# MCU.net
KiCad netlist of a schematic drawn in Altium Designer
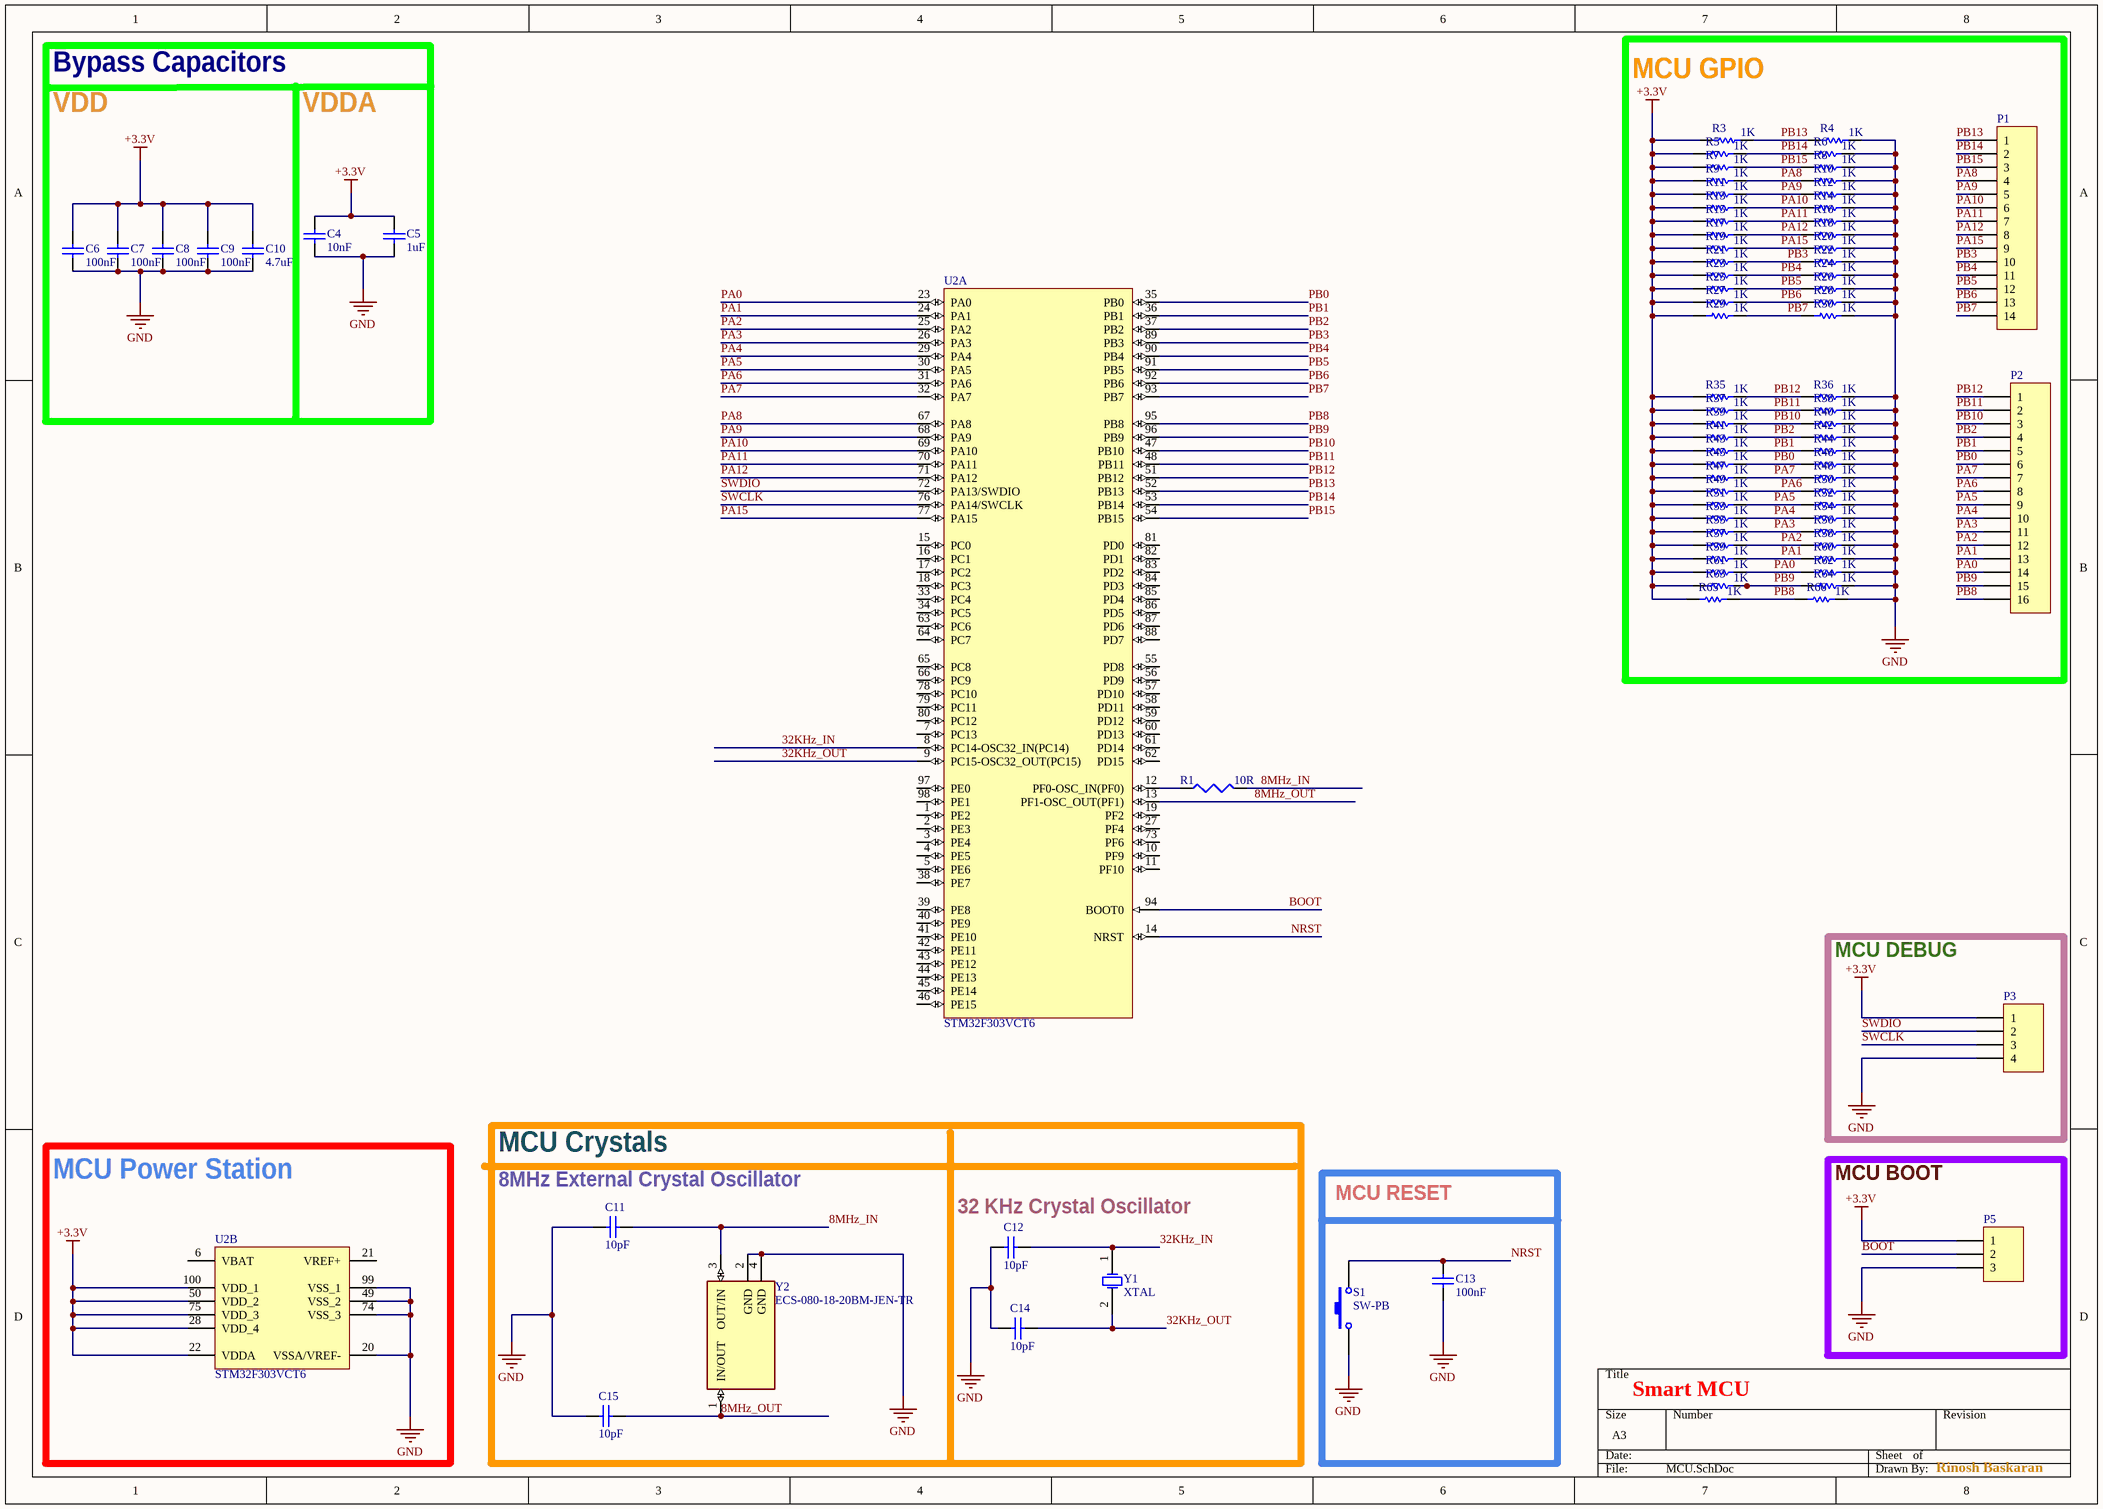
[diagram p0: MCU.SchDoc]

(export (version "E")
  (design (tool "Eeschema 10.0.6"))
  (components
    (comp (ref "C4")
      (value "10nF")
      (footprint "1608[0603]")
      (description "Capacitor (Semiconductor SIM Model)")
      (fields (field (name "Comment") "Cap Semi") (field (name "PUBLISHER") "Altium Limited"))
      (libsource (lib "Miscellaneous Devices") (part "Cap Semi"))
    )
    (comp (ref "C5")
      (value "1uF")
      (footprint "1608[0603]")
      (description "Capacitor (Semiconductor SIM Model)")
      (fields (field (name "Comment") "Cap Semi") (field (name "PUBLISHER") "Altium Limited"))
      (libsource (lib "Miscellaneous Devices") (part "Cap Semi"))
    )
    (comp (ref "C6")
      (value "100nF")
      (footprint "1608[0603]")
      (description "Capacitor (Semiconductor SIM Model)")
      (fields (field (name "Comment") "Cap Semi") (field (name "PUBLISHER") "Altium Limited"))
      (libsource (lib "Miscellaneous Devices") (part "Cap Semi"))
    )
    (comp (ref "C7")
      (value "100nF")
      (footprint "1608[0603]")
      (description "Capacitor (Semiconductor SIM Model)")
      (fields (field (name "Comment") "Cap Semi") (field (name "PUBLISHER") "Altium Limited"))
      (libsource (lib "Miscellaneous Devices") (part "Cap Semi"))
    )
    (comp (ref "C8")
      (value "100nF")
      (footprint "1608[0603]")
      (description "Capacitor (Semiconductor SIM Model)")
      (fields (field (name "Comment") "Cap Semi") (field (name "PUBLISHER") "Altium Limited"))
      (libsource (lib "Miscellaneous Devices") (part "Cap Semi"))
    )
    (comp (ref "C9")
      (value "100nF")
      (footprint "1608[0603]")
      (description "Capacitor (Semiconductor SIM Model)")
      (fields (field (name "Comment") "Cap Semi") (field (name "PUBLISHER") "Altium Limited"))
      (libsource (lib "Miscellaneous Devices") (part "Cap Semi"))
    )
    (comp (ref "C10")
      (value "4.7uF")
      (footprint "1608[0603]")
      (description "Capacitor (Semiconductor SIM Model)")
      (fields (field (name "Comment") "Cap Semi") (field (name "PUBLISHER") "Altium Limited"))
      (libsource (lib "Miscellaneous Devices") (part "Cap Semi"))
    )
    (comp (ref "C11")
      (value "10pF")
      (footprint "1608[0603]")
      (description "Capacitor (Semiconductor SIM Model)")
      (fields (field (name "Comment") "Cap Semi") (field (name "PUBLISHER") "Altium Limited"))
      (libsource (lib "Miscellaneous Devices") (part "Cap Semi"))
    )
    (comp (ref "C12")
      (value "10pF")
      (footprint "1608[0603]")
      (description "Capacitor (Semiconductor SIM Model)")
      (fields (field (name "Comment") "Cap Semi") (field (name "PUBLISHER") "Altium Limited"))
      (libsource (lib "Miscellaneous Devices") (part "Cap Semi"))
    )
    (comp (ref "C13")
      (value "100nF")
      (footprint "1608[0603]")
      (description "Capacitor (Semiconductor SIM Model)")
      (fields (field (name "Comment") "Cap Semi") (field (name "PUBLISHER") "Altium Limited"))
      (libsource (lib "Miscellaneous Devices") (part "Cap Semi"))
    )
    (comp (ref "C14")
      (value "10pF")
      (footprint "1608[0603]")
      (description "Capacitor (Semiconductor SIM Model)")
      (fields (field (name "Comment") "Cap Semi") (field (name "PUBLISHER") "Altium Limited"))
      (libsource (lib "Miscellaneous Devices") (part "Cap Semi"))
    )
    (comp (ref "C15")
      (value "10pF")
      (footprint "1608[0603]")
      (description "Capacitor (Semiconductor SIM Model)")
      (fields (field (name "Comment") "Cap Semi") (field (name "PUBLISHER") "Altium Limited"))
      (libsource (lib "Miscellaneous Devices") (part "Cap Semi"))
    )
    (comp (ref "P1")
      (value "Header 14")
      (footprint "MY_FE14")
      (description "Header, 14-Pin")
      (fields (field (name "ASID PART NUMBER") "Header 14-AS"))
      (libsource (lib "Mylib+Rev+4") (part "Header 14"))
    )
    (comp (ref "P2")
      (value "Header 16")
      (footprint "MY_FE16")
      (description "Header, 16-Pin")
      (fields (field (name "ASID PART NUMBER") "Header 16-AS"))
      (libsource (lib "Mylib+Rev+4") (part "Header 16"))
    )
    (comp (ref "P3")
      (value "Header 4")
      (footprint "My_1X04")
      (description "Header, 4-Pin")
      (fields (field (name "ASID PART NUMBER") "Header 4-AS"))
      (libsource (lib "Mylib+Rev+4") (part "Header 4"))
    )
    (comp (ref "P5")
      (value "Header 3")
      (footprint "My_1X03")
      (description "Header, 3-Pin")
      (fields (field (name "ASID PART NUMBER") "Header 3-AS"))
      (libsource (lib "Mylib+Rev+4") (part "Header 3"))
    )
    (comp (ref "R1")
      (value "10R")
      (footprint "J1-0603")
      (description "Resistor")
      (fields (field (name "Comment") "Res3") (field (name "PUBLISHER") "Altium Limited"))
      (libsource (lib "Miscellaneous Devices") (part "Res3"))
    )
    (comp (ref "R3")
      (value "1K")
      (footprint "MY_0805")
      (description "Standard resistor")
      (fields (field (name "ASID PART NUMBER") "Res-AS"))
      (libsource (lib "Mylib+Rev+4") (part "Res"))
    )
    (comp (ref "R4")
      (value "1K")
      (footprint "MY_0805")
      (description "Standard resistor")
      (fields (field (name "ASID PART NUMBER") "Res-AS"))
      (libsource (lib "Mylib+Rev+4") (part "Res"))
    )
    (comp (ref "R5")
      (value "1K")
      (footprint "MY_0805")
      (description "Standard resistor")
      (fields (field (name "ASID PART NUMBER") "Res-AS"))
      (libsource (lib "Mylib+Rev+4") (part "Res"))
    )
    (comp (ref "R6")
      (value "1K")
      (footprint "MY_0805")
      (description "Standard resistor")
      (fields (field (name "ASID PART NUMBER") "Res-AS"))
      (libsource (lib "Mylib+Rev+4") (part "Res"))
    )
    (comp (ref "R7")
      (value "1K")
      (footprint "MY_0805")
      (description "Standard resistor")
      (fields (field (name "ASID PART NUMBER") "Res-AS"))
      (libsource (lib "Mylib+Rev+4") (part "Res"))
    )
    (comp (ref "R8")
      (value "1K")
      (footprint "MY_0805")
      (description "Standard resistor")
      (fields (field (name "ASID PART NUMBER") "Res-AS"))
      (libsource (lib "Mylib+Rev+4") (part "Res"))
    )
    (comp (ref "R9")
      (value "1K")
      (footprint "MY_0805")
      (description "Standard resistor")
      (fields (field (name "ASID PART NUMBER") "Res-AS"))
      (libsource (lib "Mylib+Rev+4") (part "Res"))
    )
    (comp (ref "R10")
      (value "1K")
      (footprint "MY_0805")
      (description "Standard resistor")
      (fields (field (name "ASID PART NUMBER") "Res-AS"))
      (libsource (lib "Mylib+Rev+4") (part "Res"))
    )
    (comp (ref "R11")
      (value "1K")
      (footprint "MY_0805")
      (description "Standard resistor")
      (fields (field (name "ASID PART NUMBER") "Res-AS"))
      (libsource (lib "Mylib+Rev+4") (part "Res"))
    )
    (comp (ref "R12")
      (value "1K")
      (footprint "MY_0805")
      (description "Standard resistor")
      (fields (field (name "ASID PART NUMBER") "Res-AS"))
      (libsource (lib "Mylib+Rev+4") (part "Res"))
    )
    (comp (ref "R13")
      (value "1K")
      (footprint "MY_0805")
      (description "Standard resistor")
      (fields (field (name "ASID PART NUMBER") "Res-AS"))
      (libsource (lib "Mylib+Rev+4") (part "Res"))
    )
    (comp (ref "R14")
      (value "1K")
      (footprint "MY_0805")
      (description "Standard resistor")
      (fields (field (name "ASID PART NUMBER") "Res-AS"))
      (libsource (lib "Mylib+Rev+4") (part "Res"))
    )
    (comp (ref "R15")
      (value "1K")
      (footprint "MY_0805")
      (description "Standard resistor")
      (fields (field (name "ASID PART NUMBER") "Res-AS"))
      (libsource (lib "Mylib+Rev+4") (part "Res"))
    )
    (comp (ref "R16")
      (value "1K")
      (footprint "MY_0805")
      (description "Standard resistor")
      (fields (field (name "ASID PART NUMBER") "Res-AS"))
      (libsource (lib "Mylib+Rev+4") (part "Res"))
    )
    (comp (ref "R17")
      (value "1K")
      (footprint "MY_0805")
      (description "Standard resistor")
      (fields (field (name "ASID PART NUMBER") "Res-AS"))
      (libsource (lib "Mylib+Rev+4") (part "Res"))
    )
    (comp (ref "R18")
      (value "1K")
      (footprint "MY_0805")
      (description "Standard resistor")
      (fields (field (name "ASID PART NUMBER") "Res-AS"))
      (libsource (lib "Mylib+Rev+4") (part "Res"))
    )
    (comp (ref "R19")
      (value "1K")
      (footprint "MY_0805")
      (description "Standard resistor")
      (fields (field (name "ASID PART NUMBER") "Res-AS"))
      (libsource (lib "Mylib+Rev+4") (part "Res"))
    )
    (comp (ref "R20")
      (value "1K")
      (footprint "MY_0805")
      (description "Standard resistor")
      (fields (field (name "ASID PART NUMBER") "Res-AS"))
      (libsource (lib "Mylib+Rev+4") (part "Res"))
    )
    (comp (ref "R21")
      (value "1K")
      (footprint "MY_0805")
      (description "Standard resistor")
      (fields (field (name "ASID PART NUMBER") "Res-AS"))
      (libsource (lib "Mylib+Rev+4") (part "Res"))
    )
    (comp (ref "R22")
      (value "1K")
      (footprint "MY_0805")
      (description "Standard resistor")
      (fields (field (name "ASID PART NUMBER") "Res-AS"))
      (libsource (lib "Mylib+Rev+4") (part "Res"))
    )
    (comp (ref "R23")
      (value "1K")
      (footprint "MY_0805")
      (description "Standard resistor")
      (fields (field (name "ASID PART NUMBER") "Res-AS"))
      (libsource (lib "Mylib+Rev+4") (part "Res"))
    )
    (comp (ref "R24")
      (value "1K")
      (footprint "MY_0805")
      (description "Standard resistor")
      (fields (field (name "ASID PART NUMBER") "Res-AS"))
      (libsource (lib "Mylib+Rev+4") (part "Res"))
    )
    (comp (ref "R25")
      (value "1K")
      (footprint "MY_0805")
      (description "Standard resistor")
      (fields (field (name "ASID PART NUMBER") "Res-AS"))
      (libsource (lib "Mylib+Rev+4") (part "Res"))
    )
    (comp (ref "R26")
      (value "1K")
      (footprint "MY_0805")
      (description "Standard resistor")
      (fields (field (name "ASID PART NUMBER") "Res-AS"))
      (libsource (lib "Mylib+Rev+4") (part "Res"))
    )
    (comp (ref "R27")
      (value "1K")
      (footprint "MY_0805")
      (description "Standard resistor")
      (fields (field (name "ASID PART NUMBER") "Res-AS"))
      (libsource (lib "Mylib+Rev+4") (part "Res"))
    )
    (comp (ref "R28")
      (value "1K")
      (footprint "MY_0805")
      (description "Standard resistor")
      (fields (field (name "ASID PART NUMBER") "Res-AS"))
      (libsource (lib "Mylib+Rev+4") (part "Res"))
    )
    (comp (ref "R29")
      (value "1K")
      (footprint "MY_0805")
      (description "Standard resistor")
      (fields (field (name "ASID PART NUMBER") "Res-AS"))
      (libsource (lib "Mylib+Rev+4") (part "Res"))
    )
    (comp (ref "R30")
      (value "1K")
      (footprint "MY_0805")
      (description "Standard resistor")
      (fields (field (name "ASID PART NUMBER") "Res-AS"))
      (libsource (lib "Mylib+Rev+4") (part "Res"))
    )
    (comp (ref "R35")
      (value "1K")
      (footprint "MY_0805")
      (description "Standard resistor")
      (fields (field (name "ASID PART NUMBER") "Res-AS"))
      (libsource (lib "Mylib+Rev+4") (part "Res"))
    )
    (comp (ref "R36")
      (value "1K")
      (footprint "MY_0805")
      (description "Standard resistor")
      (fields (field (name "ASID PART NUMBER") "Res-AS"))
      (libsource (lib "Mylib+Rev+4") (part "Res"))
    )
    (comp (ref "R37")
      (value "1K")
      (footprint "MY_0805")
      (description "Standard resistor")
      (fields (field (name "ASID PART NUMBER") "Res-AS"))
      (libsource (lib "Mylib+Rev+4") (part "Res"))
    )
    (comp (ref "R38")
      (value "1K")
      (footprint "MY_0805")
      (description "Standard resistor")
      (fields (field (name "ASID PART NUMBER") "Res-AS"))
      (libsource (lib "Mylib+Rev+4") (part "Res"))
    )
    (comp (ref "R39")
      (value "1K")
      (footprint "MY_0805")
      (description "Standard resistor")
      (fields (field (name "ASID PART NUMBER") "Res-AS"))
      (libsource (lib "Mylib+Rev+4") (part "Res"))
    )
    (comp (ref "R40")
      (value "1K")
      (footprint "MY_0805")
      (description "Standard resistor")
      (fields (field (name "ASID PART NUMBER") "Res-AS"))
      (libsource (lib "Mylib+Rev+4") (part "Res"))
    )
    (comp (ref "R41")
      (value "1K")
      (footprint "MY_0805")
      (description "Standard resistor")
      (fields (field (name "ASID PART NUMBER") "Res-AS"))
      (libsource (lib "Mylib+Rev+4") (part "Res"))
    )
    (comp (ref "R42")
      (value "1K")
      (footprint "MY_0805")
      (description "Standard resistor")
      (fields (field (name "ASID PART NUMBER") "Res-AS"))
      (libsource (lib "Mylib+Rev+4") (part "Res"))
    )
    (comp (ref "R43")
      (value "1K")
      (footprint "MY_0805")
      (description "Standard resistor")
      (fields (field (name "ASID PART NUMBER") "Res-AS"))
      (libsource (lib "Mylib+Rev+4") (part "Res"))
    )
    (comp (ref "R44")
      (value "1K")
      (footprint "MY_0805")
      (description "Standard resistor")
      (fields (field (name "ASID PART NUMBER") "Res-AS"))
      (libsource (lib "Mylib+Rev+4") (part "Res"))
    )
    (comp (ref "R45")
      (value "1K")
      (footprint "MY_0805")
      (description "Standard resistor")
      (fields (field (name "ASID PART NUMBER") "Res-AS"))
      (libsource (lib "Mylib+Rev+4") (part "Res"))
    )
    (comp (ref "R46")
      (value "1K")
      (footprint "MY_0805")
      (description "Standard resistor")
      (fields (field (name "ASID PART NUMBER") "Res-AS"))
      (libsource (lib "Mylib+Rev+4") (part "Res"))
    )
    (comp (ref "R47")
      (value "1K")
      (footprint "MY_0805")
      (description "Standard resistor")
      (fields (field (name "ASID PART NUMBER") "Res-AS"))
      (libsource (lib "Mylib+Rev+4") (part "Res"))
    )
    (comp (ref "R48")
      (value "1K")
      (footprint "MY_0805")
      (description "Standard resistor")
      (fields (field (name "ASID PART NUMBER") "Res-AS"))
      (libsource (lib "Mylib+Rev+4") (part "Res"))
    )
    (comp (ref "R49")
      (value "1K")
      (footprint "MY_0805")
      (description "Standard resistor")
      (fields (field (name "ASID PART NUMBER") "Res-AS"))
      (libsource (lib "Mylib+Rev+4") (part "Res"))
    )
    (comp (ref "R50")
      (value "1K")
      (footprint "MY_0805")
      (description "Standard resistor")
      (fields (field (name "ASID PART NUMBER") "Res-AS"))
      (libsource (lib "Mylib+Rev+4") (part "Res"))
    )
    (comp (ref "R51")
      (value "1K")
      (footprint "MY_0805")
      (description "Standard resistor")
      (fields (field (name "ASID PART NUMBER") "Res-AS"))
      (libsource (lib "Mylib+Rev+4") (part "Res"))
    )
    (comp (ref "R52")
      (value "1K")
      (footprint "MY_0805")
      (description "Standard resistor")
      (fields (field (name "ASID PART NUMBER") "Res-AS"))
      (libsource (lib "Mylib+Rev+4") (part "Res"))
    )
    (comp (ref "R53")
      (value "1K")
      (footprint "MY_0805")
      (description "Standard resistor")
      (fields (field (name "ASID PART NUMBER") "Res-AS"))
      (libsource (lib "Mylib+Rev+4") (part "Res"))
    )
    (comp (ref "R54")
      (value "1K")
      (footprint "MY_0805")
      (description "Standard resistor")
      (fields (field (name "ASID PART NUMBER") "Res-AS"))
      (libsource (lib "Mylib+Rev+4") (part "Res"))
    )
    (comp (ref "R55")
      (value "1K")
      (footprint "MY_0805")
      (description "Standard resistor")
      (fields (field (name "ASID PART NUMBER") "Res-AS"))
      (libsource (lib "Mylib+Rev+4") (part "Res"))
    )
    (comp (ref "R56")
      (value "1K")
      (footprint "MY_0805")
      (description "Standard resistor")
      (fields (field (name "ASID PART NUMBER") "Res-AS"))
      (libsource (lib "Mylib+Rev+4") (part "Res"))
    )
    (comp (ref "R57")
      (value "1K")
      (footprint "MY_0805")
      (description "Standard resistor")
      (fields (field (name "ASID PART NUMBER") "Res-AS"))
      (libsource (lib "Mylib+Rev+4") (part "Res"))
    )
    (comp (ref "R58")
      (value "1K")
      (footprint "MY_0805")
      (description "Standard resistor")
      (fields (field (name "ASID PART NUMBER") "Res-AS"))
      (libsource (lib "Mylib+Rev+4") (part "Res"))
    )
    (comp (ref "R59")
      (value "1K")
      (footprint "MY_0805")
      (description "Standard resistor")
      (fields (field (name "ASID PART NUMBER") "Res-AS"))
      (libsource (lib "Mylib+Rev+4") (part "Res"))
    )
    (comp (ref "R60")
      (value "1K")
      (footprint "MY_0805")
      (description "Standard resistor")
      (fields (field (name "ASID PART NUMBER") "Res-AS"))
      (libsource (lib "Mylib+Rev+4") (part "Res"))
    )
    (comp (ref "R61")
      (value "1K")
      (footprint "MY_0805")
      (description "Standard resistor")
      (fields (field (name "ASID PART NUMBER") "Res-AS"))
      (libsource (lib "Mylib+Rev+4") (part "Res"))
    )
    (comp (ref "R62")
      (value "1K")
      (footprint "MY_0805")
      (description "Standard resistor")
      (fields (field (name "ASID PART NUMBER") "Res-AS"))
      (libsource (lib "Mylib+Rev+4") (part "Res"))
    )
    (comp (ref "R63")
      (value "1K")
      (footprint "MY_0805")
      (description "Standard resistor")
      (fields (field (name "ASID PART NUMBER") "Res-AS"))
      (libsource (lib "Mylib+Rev+4") (part "Res"))
    )
    (comp (ref "R64")
      (value "1K")
      (footprint "MY_0805")
      (description "Standard resistor")
      (fields (field (name "ASID PART NUMBER") "Res-AS"))
      (libsource (lib "Mylib+Rev+4") (part "Res"))
    )
    (comp (ref "R65")
      (value "1K")
      (footprint "MY_0805")
      (description "Standard resistor")
      (fields (field (name "ASID PART NUMBER") "Res-AS"))
      (libsource (lib "Mylib+Rev+4") (part "Res"))
    )
    (comp (ref "R66")
      (value "1K")
      (footprint "MY_0805")
      (description "Standard resistor")
      (fields (field (name "ASID PART NUMBER") "Res-AS"))
      (libsource (lib "Mylib+Rev+4") (part "Res"))
    )
    (comp (ref "S1")
      (value "SW-PB")
      (footprint "SPST-2")
      (description "Switch")
      (fields (field (name "PUBLISHER") "Altium Limited"))
      (libsource (lib "Miscellaneous Devices") (part "SW-PB"))
    )
    (comp (ref "U2")
      (value "STM32F303VCT6")
      (footprint "STM-LQFP100_N")
      (libsource (lib "STMicroelectronics STM32 F3") (part "STM32F303VCT6"))
    )
    (comp (ref "Y1")
      (value "XTAL")
      (footprint "R38")
      (description "Crystal Oscillator")
      (fields (field (name "PUBLISHER") "Altium Limited"))
      (libsource (lib "Miscellaneous Devices") (part "XTAL"))
    )
    (comp (ref "Y2")
      (value "ECS-080-18-20BM-JEN-TR")
      (footprint "ECS_ECS-060-18-20BM-JEN-TR")
      (description "8 MHz Â±20ppm Crystal 18pF 60 Ohms 4-SMD, No Lead")
      (fields (field (name "MF") "ECS Inc."))
      (libsource (lib "ECS-080-18-20BM-JEN-TR") (part "ECS-080-18-20BM-JEN-TR"))
    )
  )
  (nets
    (net (code "1") (name "+3.3V") (class "Default")
      (node (ref "C10") (pin "2") (pinfunction "2_2") (pintype "passive"))
      (node (ref "C4") (pin "2") (pinfunction "2_2") (pintype "passive"))
      (node (ref "C5") (pin "2") (pinfunction "2_2") (pintype "passive"))
      (node (ref "C6") (pin "2") (pinfunction "2_2") (pintype "passive"))
      (node (ref "C7") (pin "2") (pinfunction "2_2") (pintype "passive"))
      (node (ref "C8") (pin "2") (pinfunction "2_2") (pintype "passive"))
      (node (ref "C9") (pin "2") (pinfunction "2_2") (pintype "passive"))
      (node (ref "P3") (pin "1") (pinfunction "1_1") (pintype "passive"))
      (node (ref "P5") (pin "1") (pinfunction "1_1") (pintype "passive"))
      (node (ref "R11") (pin "1") (pinfunction "1_1") (pintype "passive"))
      (node (ref "R13") (pin "1") (pinfunction "1_1") (pintype "passive"))
      (node (ref "R15") (pin "1") (pinfunction "1_1") (pintype "passive"))
      (node (ref "R17") (pin "1") (pinfunction "1_1") (pintype "passive"))
      (node (ref "R19") (pin "1") (pinfunction "1_1") (pintype "passive"))
      (node (ref "R21") (pin "1") (pinfunction "1_1") (pintype "passive"))
      (node (ref "R23") (pin "1") (pinfunction "1_1") (pintype "passive"))
      (node (ref "R25") (pin "1") (pinfunction "1_1") (pintype "passive"))
      (node (ref "R27") (pin "1") (pinfunction "1_1") (pintype "passive"))
      (node (ref "R29") (pin "1") (pinfunction "1_1") (pintype "passive"))
      (node (ref "R3") (pin "1") (pinfunction "1_1") (pintype "passive"))
      (node (ref "R35") (pin "1") (pinfunction "1_1") (pintype "passive"))
      (node (ref "R37") (pin "1") (pinfunction "1_1") (pintype "passive"))
      (node (ref "R39") (pin "1") (pinfunction "1_1") (pintype "passive"))
      (node (ref "R41") (pin "1") (pinfunction "1_1") (pintype "passive"))
      (node (ref "R43") (pin "1") (pinfunction "1_1") (pintype "passive"))
      (node (ref "R45") (pin "1") (pinfunction "1_1") (pintype "passive"))
      (node (ref "R47") (pin "1") (pinfunction "1_1") (pintype "passive"))
      (node (ref "R49") (pin "1") (pinfunction "1_1") (pintype "passive"))
      (node (ref "R5") (pin "1") (pinfunction "1_1") (pintype "passive"))
      (node (ref "R51") (pin "1") (pinfunction "1_1") (pintype "passive"))
      (node (ref "R53") (pin "1") (pinfunction "1_1") (pintype "passive"))
      (node (ref "R55") (pin "1") (pinfunction "1_1") (pintype "passive"))
      (node (ref "R57") (pin "1") (pinfunction "1_1") (pintype "passive"))
      (node (ref "R59") (pin "1") (pinfunction "1_1") (pintype "passive"))
      (node (ref "R61") (pin "1") (pinfunction "1_1") (pintype "passive"))
      (node (ref "R63") (pin "1") (pinfunction "1_1") (pintype "passive"))
      (node (ref "R65") (pin "1") (pinfunction "1_1") (pintype "passive"))
      (node (ref "R7") (pin "1") (pinfunction "1_1") (pintype "passive"))
      (node (ref "R9") (pin "1") (pinfunction "1_1") (pintype "passive"))
      (node (ref "U2") (pin "100") (pinfunction "VDD_1_100") (pintype "power_in"))
      (node (ref "U2") (pin "22") (pinfunction "VDDA_22") (pintype "power_in"))
      (node (ref "U2") (pin "28") (pinfunction "VDD_4_28") (pintype "power_in"))
      (node (ref "U2") (pin "50") (pinfunction "VDD_2_50") (pintype "power_in"))
      (node (ref "U2") (pin "75") (pinfunction "VDD_3_75") (pintype "power_in"))
    )
    (net (code "2") (name "/8MHz_IN") (class "Default")
      (node (ref "C11") (pin "1") (pinfunction "1_1") (pintype "passive"))
      (node (ref "R1") (pin "2") (pinfunction "2_2") (pintype "passive"))
      (node (ref "Y2") (pin "3") (pinfunction "OUT/IN_3") (pintype "bidirectional"))
    )
    (net (code "3") (name "/8MHz_OUT") (class "Default")
      (node (ref "C15") (pin "1") (pinfunction "1_1") (pintype "passive"))
      (node (ref "U2") (pin "13") (pinfunction "PF1-OSC_OUT(PF1)_13") (pintype "bidirectional"))
      (node (ref "Y2") (pin "1") (pinfunction "IN/OUT_1") (pintype "bidirectional"))
    )
    (net (code "4") (name "/32KHz_IN") (class "Default")
      (node (ref "C12") (pin "1") (pinfunction "1_1") (pintype "passive"))
      (node (ref "U2") (pin "8") (pinfunction "PC14-OSC32_IN(PC14)_8") (pintype "bidirectional"))
      (node (ref "Y1") (pin "1") (pinfunction "OSC1_1") (pintype "passive"))
    )
    (net (code "5") (name "/32KHz_OUT") (class "Default")
      (node (ref "C14") (pin "1") (pinfunction "1_1") (pintype "passive"))
      (node (ref "U2") (pin "9") (pinfunction "PC15-OSC32_OUT(PC15)_9") (pintype "bidirectional"))
      (node (ref "Y1") (pin "2") (pinfunction "OSC2_2") (pintype "passive"))
    )
    (net (code "6") (name "/BOOT") (class "Default")
      (node (ref "P5") (pin "2") (pinfunction "2_2") (pintype "passive"))
      (node (ref "U2") (pin "94") (pinfunction "BOOT0_94") (pintype "input"))
    )
    (net (code "7") (name "/NRST") (class "Default")
      (node (ref "C13") (pin "1") (pinfunction "1_1") (pintype "passive"))
      (node (ref "S1") (pin "2") (pinfunction "2_2") (pintype "passive"))
      (node (ref "U2") (pin "14") (pinfunction "NRST_14") (pintype "bidirectional"))
    )
    (net (code "8") (name "/PA0") (class "Default")
      (node (ref "P2") (pin "14") (pinfunction "14_14") (pintype "passive"))
      (node (ref "R61") (pin "2") (pinfunction "2_2") (pintype "passive"))
      (node (ref "R62") (pin "1") (pinfunction "1_1") (pintype "passive"))
      (node (ref "U2") (pin "23") (pinfunction "PA0_23") (pintype "bidirectional"))
    )
    (net (code "9") (name "/PA1") (class "Default")
      (node (ref "P2") (pin "13") (pinfunction "13_13") (pintype "passive"))
      (node (ref "R59") (pin "2") (pinfunction "2_2") (pintype "passive"))
      (node (ref "R60") (pin "1") (pinfunction "1_1") (pintype "passive"))
      (node (ref "U2") (pin "24") (pinfunction "PA1_24") (pintype "bidirectional"))
    )
    (net (code "10") (name "/PA2") (class "Default")
      (node (ref "P2") (pin "12") (pinfunction "12_12") (pintype "passive"))
      (node (ref "R57") (pin "2") (pinfunction "2_2") (pintype "passive"))
      (node (ref "R58") (pin "1") (pinfunction "1_1") (pintype "passive"))
      (node (ref "U2") (pin "25") (pinfunction "PA2_25") (pintype "bidirectional"))
    )
    (net (code "11") (name "/PA3") (class "Default")
      (node (ref "P2") (pin "11") (pinfunction "11_11") (pintype "passive"))
      (node (ref "R55") (pin "2") (pinfunction "2_2") (pintype "passive"))
      (node (ref "R56") (pin "1") (pinfunction "1_1") (pintype "passive"))
      (node (ref "U2") (pin "26") (pinfunction "PA3_26") (pintype "bidirectional"))
    )
    (net (code "12") (name "/PA4") (class "Default")
      (node (ref "P2") (pin "10") (pinfunction "10_10") (pintype "passive"))
      (node (ref "R53") (pin "2") (pinfunction "2_2") (pintype "passive"))
      (node (ref "R54") (pin "1") (pinfunction "1_1") (pintype "passive"))
      (node (ref "U2") (pin "29") (pinfunction "PA4_29") (pintype "bidirectional"))
    )
    (net (code "13") (name "/PA5") (class "Default")
      (node (ref "P2") (pin "9") (pinfunction "9_9") (pintype "passive"))
      (node (ref "R51") (pin "2") (pinfunction "2_2") (pintype "passive"))
      (node (ref "R52") (pin "1") (pinfunction "1_1") (pintype "passive"))
      (node (ref "U2") (pin "30") (pinfunction "PA5_30") (pintype "bidirectional"))
    )
    (net (code "14") (name "/PA6") (class "Default")
      (node (ref "P2") (pin "8") (pinfunction "8_8") (pintype "passive"))
      (node (ref "R49") (pin "2") (pinfunction "2_2") (pintype "passive"))
      (node (ref "R50") (pin "1") (pinfunction "1_1") (pintype "passive"))
      (node (ref "U2") (pin "31") (pinfunction "PA6_31") (pintype "bidirectional"))
    )
    (net (code "15") (name "/PA7") (class "Default")
      (node (ref "P2") (pin "7") (pinfunction "7_7") (pintype "passive"))
      (node (ref "R47") (pin "2") (pinfunction "2_2") (pintype "passive"))
      (node (ref "R48") (pin "1") (pinfunction "1_1") (pintype "passive"))
      (node (ref "U2") (pin "32") (pinfunction "PA7_32") (pintype "bidirectional"))
    )
    (net (code "16") (name "/PA8") (class "Default")
      (node (ref "P1") (pin "4") (pinfunction "4_4") (pintype "passive"))
      (node (ref "R10") (pin "1") (pinfunction "1_1") (pintype "passive"))
      (node (ref "R9") (pin "2") (pinfunction "2_2") (pintype "passive"))
      (node (ref "U2") (pin "67") (pinfunction "PA8_67") (pintype "bidirectional"))
    )
    (net (code "17") (name "/PA9") (class "Default")
      (node (ref "P1") (pin "5") (pinfunction "5_5") (pintype "passive"))
      (node (ref "R11") (pin "2") (pinfunction "2_2") (pintype "passive"))
      (node (ref "R12") (pin "1") (pinfunction "1_1") (pintype "passive"))
      (node (ref "U2") (pin "68") (pinfunction "PA9_68") (pintype "bidirectional"))
    )
    (net (code "18") (name "/PA10") (class "Default")
      (node (ref "P1") (pin "6") (pinfunction "6_6") (pintype "passive"))
      (node (ref "R13") (pin "2") (pinfunction "2_2") (pintype "passive"))
      (node (ref "R14") (pin "1") (pinfunction "1_1") (pintype "passive"))
      (node (ref "U2") (pin "69") (pinfunction "PA10_69") (pintype "bidirectional"))
    )
    (net (code "19") (name "/PA11") (class "Default")
      (node (ref "P1") (pin "7") (pinfunction "7_7") (pintype "passive"))
      (node (ref "R15") (pin "2") (pinfunction "2_2") (pintype "passive"))
      (node (ref "R16") (pin "1") (pinfunction "1_1") (pintype "passive"))
      (node (ref "U2") (pin "70") (pinfunction "PA11_70") (pintype "bidirectional"))
    )
    (net (code "20") (name "/PA12") (class "Default")
      (node (ref "P1") (pin "8") (pinfunction "8_8") (pintype "passive"))
      (node (ref "R17") (pin "2") (pinfunction "2_2") (pintype "passive"))
      (node (ref "R18") (pin "1") (pinfunction "1_1") (pintype "passive"))
      (node (ref "U2") (pin "71") (pinfunction "PA12_71") (pintype "bidirectional"))
    )
    (net (code "21") (name "/PA15") (class "Default")
      (node (ref "P1") (pin "9") (pinfunction "9_9") (pintype "passive"))
      (node (ref "R19") (pin "2") (pinfunction "2_2") (pintype "passive"))
      (node (ref "R20") (pin "1") (pinfunction "1_1") (pintype "passive"))
      (node (ref "U2") (pin "77") (pinfunction "PA15_77") (pintype "bidirectional"))
    )
    (net (code "22") (name "/PB0") (class "Default")
      (node (ref "P2") (pin "6") (pinfunction "6_6") (pintype "passive"))
      (node (ref "R45") (pin "2") (pinfunction "2_2") (pintype "passive"))
      (node (ref "R46") (pin "1") (pinfunction "1_1") (pintype "passive"))
      (node (ref "U2") (pin "35") (pinfunction "PB0_35") (pintype "bidirectional"))
    )
    (net (code "23") (name "/PB1") (class "Default")
      (node (ref "P2") (pin "5") (pinfunction "5_5") (pintype "passive"))
      (node (ref "R43") (pin "2") (pinfunction "2_2") (pintype "passive"))
      (node (ref "R44") (pin "1") (pinfunction "1_1") (pintype "passive"))
      (node (ref "U2") (pin "36") (pinfunction "PB1_36") (pintype "bidirectional"))
    )
    (net (code "24") (name "/PB2") (class "Default")
      (node (ref "P2") (pin "4") (pinfunction "4_4") (pintype "passive"))
      (node (ref "R41") (pin "2") (pinfunction "2_2") (pintype "passive"))
      (node (ref "R42") (pin "1") (pinfunction "1_1") (pintype "passive"))
      (node (ref "U2") (pin "37") (pinfunction "PB2_37") (pintype "bidirectional"))
    )
    (net (code "25") (name "/PB3") (class "Default")
      (node (ref "P1") (pin "10") (pinfunction "10_10") (pintype "passive"))
      (node (ref "R21") (pin "2") (pinfunction "2_2") (pintype "passive"))
      (node (ref "R22") (pin "1") (pinfunction "1_1") (pintype "passive"))
      (node (ref "U2") (pin "89") (pinfunction "PB3_89") (pintype "bidirectional"))
    )
    (net (code "26") (name "/PB4") (class "Default")
      (node (ref "P1") (pin "11") (pinfunction "11_11") (pintype "passive"))
      (node (ref "R23") (pin "2") (pinfunction "2_2") (pintype "passive"))
      (node (ref "R24") (pin "1") (pinfunction "1_1") (pintype "passive"))
      (node (ref "U2") (pin "90") (pinfunction "PB4_90") (pintype "bidirectional"))
    )
    (net (code "27") (name "/PB5") (class "Default")
      (node (ref "P1") (pin "12") (pinfunction "12_12") (pintype "passive"))
      (node (ref "R25") (pin "2") (pinfunction "2_2") (pintype "passive"))
      (node (ref "R26") (pin "1") (pinfunction "1_1") (pintype "passive"))
      (node (ref "U2") (pin "91") (pinfunction "PB5_91") (pintype "bidirectional"))
    )
    (net (code "28") (name "/PB6") (class "Default")
      (node (ref "P1") (pin "13") (pinfunction "13_13") (pintype "passive"))
      (node (ref "R27") (pin "2") (pinfunction "2_2") (pintype "passive"))
      (node (ref "R28") (pin "1") (pinfunction "1_1") (pintype "passive"))
      (node (ref "U2") (pin "92") (pinfunction "PB6_92") (pintype "bidirectional"))
    )
    (net (code "29") (name "/PB7") (class "Default")
      (node (ref "P1") (pin "14") (pinfunction "14_14") (pintype "passive"))
      (node (ref "R29") (pin "2") (pinfunction "2_2") (pintype "passive"))
      (node (ref "R30") (pin "1") (pinfunction "1_1") (pintype "passive"))
      (node (ref "U2") (pin "93") (pinfunction "PB7_93") (pintype "bidirectional"))
    )
    (net (code "30") (name "/PB8") (class "Default")
      (node (ref "P2") (pin "16") (pinfunction "16_16") (pintype "passive"))
      (node (ref "R65") (pin "2") (pinfunction "2_2") (pintype "passive"))
      (node (ref "R66") (pin "1") (pinfunction "1_1") (pintype "passive"))
      (node (ref "U2") (pin "95") (pinfunction "PB8_95") (pintype "bidirectional"))
    )
    (net (code "31") (name "/PB9") (class "Default")
      (node (ref "P2") (pin "15") (pinfunction "15_15") (pintype "passive"))
      (node (ref "R63") (pin "2") (pinfunction "2_2") (pintype "passive"))
      (node (ref "R64") (pin "1") (pinfunction "1_1") (pintype "passive"))
      (node (ref "U2") (pin "96") (pinfunction "PB9_96") (pintype "bidirectional"))
    )
    (net (code "32") (name "/PB10") (class "Default")
      (node (ref "P2") (pin "3") (pinfunction "3_3") (pintype "passive"))
      (node (ref "R39") (pin "2") (pinfunction "2_2") (pintype "passive"))
      (node (ref "R40") (pin "1") (pinfunction "1_1") (pintype "passive"))
      (node (ref "U2") (pin "47") (pinfunction "PB10_47") (pintype "bidirectional"))
    )
    (net (code "33") (name "/PB11") (class "Default")
      (node (ref "P2") (pin "2") (pinfunction "2_2") (pintype "passive"))
      (node (ref "R37") (pin "2") (pinfunction "2_2") (pintype "passive"))
      (node (ref "R38") (pin "1") (pinfunction "1_1") (pintype "passive"))
      (node (ref "U2") (pin "48") (pinfunction "PB11_48") (pintype "bidirectional"))
    )
    (net (code "34") (name "/PB12") (class "Default")
      (node (ref "P2") (pin "1") (pinfunction "1_1") (pintype "passive"))
      (node (ref "R35") (pin "2") (pinfunction "2_2") (pintype "passive"))
      (node (ref "R36") (pin "1") (pinfunction "1_1") (pintype "passive"))
      (node (ref "U2") (pin "51") (pinfunction "PB12_51") (pintype "bidirectional"))
    )
    (net (code "35") (name "/PB13") (class "Default")
      (node (ref "P1") (pin "1") (pinfunction "1_1") (pintype "passive"))
      (node (ref "R3") (pin "2") (pinfunction "2_2") (pintype "passive"))
      (node (ref "R4") (pin "1") (pinfunction "1_1") (pintype "passive"))
      (node (ref "U2") (pin "52") (pinfunction "PB13_52") (pintype "bidirectional"))
    )
    (net (code "36") (name "/PB14") (class "Default")
      (node (ref "P1") (pin "2") (pinfunction "2_2") (pintype "passive"))
      (node (ref "R5") (pin "2") (pinfunction "2_2") (pintype "passive"))
      (node (ref "R6") (pin "1") (pinfunction "1_1") (pintype "passive"))
      (node (ref "U2") (pin "53") (pinfunction "PB14_53") (pintype "bidirectional"))
    )
    (net (code "37") (name "/PB15") (class "Default")
      (node (ref "P1") (pin "3") (pinfunction "3_3") (pintype "passive"))
      (node (ref "R7") (pin "2") (pinfunction "2_2") (pintype "passive"))
      (node (ref "R8") (pin "1") (pinfunction "1_1") (pintype "passive"))
      (node (ref "U2") (pin "54") (pinfunction "PB15_54") (pintype "bidirectional"))
    )
    (net (code "38") (name "/SWCLK") (class "Default")
      (node (ref "P3") (pin "3") (pinfunction "3_3") (pintype "passive"))
      (node (ref "U2") (pin "76") (pinfunction "PA14/SWCLK_76") (pintype "bidirectional"))
    )
    (net (code "39") (name "/SWDIO") (class "Default")
      (node (ref "P3") (pin "2") (pinfunction "2_2") (pintype "passive"))
      (node (ref "U2") (pin "72") (pinfunction "PA13/SWDIO_72") (pintype "bidirectional"))
    )
    (net (code "40") (name "GND") (class "Default")
      (node (ref "C10") (pin "1") (pinfunction "1_1") (pintype "passive"))
      (node (ref "C11") (pin "2") (pinfunction "2_2") (pintype "passive"))
      (node (ref "C12") (pin "2") (pinfunction "2_2") (pintype "passive"))
      (node (ref "C13") (pin "2") (pinfunction "2_2") (pintype "passive"))
      (node (ref "C14") (pin "2") (pinfunction "2_2") (pintype "passive"))
      (node (ref "C15") (pin "2") (pinfunction "2_2") (pintype "passive"))
      (node (ref "C4") (pin "1") (pinfunction "1_1") (pintype "passive"))
      (node (ref "C5") (pin "1") (pinfunction "1_1") (pintype "passive"))
      (node (ref "C6") (pin "1") (pinfunction "1_1") (pintype "passive"))
      (node (ref "C7") (pin "1") (pinfunction "1_1") (pintype "passive"))
      (node (ref "C8") (pin "1") (pinfunction "1_1") (pintype "passive"))
      (node (ref "C9") (pin "1") (pinfunction "1_1") (pintype "passive"))
      (node (ref "P3") (pin "4") (pinfunction "4_4") (pintype "passive"))
      (node (ref "P5") (pin "3") (pinfunction "3_3") (pintype "passive"))
      (node (ref "R10") (pin "2") (pinfunction "2_2") (pintype "passive"))
      (node (ref "R12") (pin "2") (pinfunction "2_2") (pintype "passive"))
      (node (ref "R14") (pin "2") (pinfunction "2_2") (pintype "passive"))
      (node (ref "R16") (pin "2") (pinfunction "2_2") (pintype "passive"))
      (node (ref "R18") (pin "2") (pinfunction "2_2") (pintype "passive"))
      (node (ref "R20") (pin "2") (pinfunction "2_2") (pintype "passive"))
      (node (ref "R22") (pin "2") (pinfunction "2_2") (pintype "passive"))
      (node (ref "R24") (pin "2") (pinfunction "2_2") (pintype "passive"))
      (node (ref "R26") (pin "2") (pinfunction "2_2") (pintype "passive"))
      (node (ref "R28") (pin "2") (pinfunction "2_2") (pintype "passive"))
      (node (ref "R30") (pin "2") (pinfunction "2_2") (pintype "passive"))
      (node (ref "R36") (pin "2") (pinfunction "2_2") (pintype "passive"))
      (node (ref "R38") (pin "2") (pinfunction "2_2") (pintype "passive"))
      (node (ref "R4") (pin "2") (pinfunction "2_2") (pintype "passive"))
      (node (ref "R40") (pin "2") (pinfunction "2_2") (pintype "passive"))
      (node (ref "R42") (pin "2") (pinfunction "2_2") (pintype "passive"))
      (node (ref "R44") (pin "2") (pinfunction "2_2") (pintype "passive"))
      (node (ref "R46") (pin "2") (pinfunction "2_2") (pintype "passive"))
      (node (ref "R48") (pin "2") (pinfunction "2_2") (pintype "passive"))
      (node (ref "R50") (pin "2") (pinfunction "2_2") (pintype "passive"))
      (node (ref "R52") (pin "2") (pinfunction "2_2") (pintype "passive"))
      (node (ref "R54") (pin "2") (pinfunction "2_2") (pintype "passive"))
      (node (ref "R56") (pin "2") (pinfunction "2_2") (pintype "passive"))
      (node (ref "R58") (pin "2") (pinfunction "2_2") (pintype "passive"))
      (node (ref "R6") (pin "2") (pinfunction "2_2") (pintype "passive"))
      (node (ref "R60") (pin "2") (pinfunction "2_2") (pintype "passive"))
      (node (ref "R62") (pin "2") (pinfunction "2_2") (pintype "passive"))
      (node (ref "R64") (pin "2") (pinfunction "2_2") (pintype "passive"))
      (node (ref "R66") (pin "2") (pinfunction "2_2") (pintype "passive"))
      (node (ref "R8") (pin "2") (pinfunction "2_2") (pintype "passive"))
      (node (ref "S1") (pin "1") (pinfunction "1_1") (pintype "passive"))
      (node (ref "U2") (pin "20") (pinfunction "VSSA/VREF-_20") (pintype "power_in"))
      (node (ref "U2") (pin "49") (pinfunction "VSS_2_49") (pintype "power_in"))
      (node (ref "U2") (pin "74") (pinfunction "VSS_3_74") (pintype "power_in"))
      (node (ref "U2") (pin "99") (pinfunction "VSS_1_99") (pintype "power_in"))
      (node (ref "Y2") (pin "2") (pinfunction "GND_2") (pintype "power_in"))
      (node (ref "Y2") (pin "4") (pinfunction "GND_4") (pintype "power_in"))
    )
    (net (code "41") (name "Net-(U2A-PF0-OSC_IN(PF0))") (class "Default")
      (node (ref "R1") (pin "1") (pinfunction "1_1") (pintype "passive"))
      (node (ref "U2") (pin "12") (pinfunction "PF0-OSC_IN(PF0)_12") (pintype "bidirectional"))
    )
    (net (code "42") (name "unconnected-(U2A-PC0-Pad15)") (class "Default")
      (node (ref "U2") (pin "15") (pinfunction "PC0_15") (pintype "bidirectional"))
    )
    (net (code "43") (name "unconnected-(U2A-PC1-Pad16)") (class "Default")
      (node (ref "U2") (pin "16") (pinfunction "PC1_16") (pintype "bidirectional"))
    )
    (net (code "44") (name "unconnected-(U2A-PC2-Pad17)") (class "Default")
      (node (ref "U2") (pin "17") (pinfunction "PC2_17") (pintype "bidirectional"))
    )
    (net (code "45") (name "unconnected-(U2A-PC3-Pad18)") (class "Default")
      (node (ref "U2") (pin "18") (pinfunction "PC3_18") (pintype "bidirectional"))
    )
    (net (code "46") (name "unconnected-(U2A-PC4-Pad33)") (class "Default")
      (node (ref "U2") (pin "33") (pinfunction "PC4_33") (pintype "bidirectional"))
    )
    (net (code "47") (name "unconnected-(U2A-PC5-Pad34)") (class "Default")
      (node (ref "U2") (pin "34") (pinfunction "PC5_34") (pintype "bidirectional"))
    )
    (net (code "48") (name "unconnected-(U2A-PC6-Pad63)") (class "Default")
      (node (ref "U2") (pin "63") (pinfunction "PC6_63") (pintype "bidirectional"))
    )
    (net (code "49") (name "unconnected-(U2A-PC7-Pad64)") (class "Default")
      (node (ref "U2") (pin "64") (pinfunction "PC7_64") (pintype "bidirectional"))
    )
    (net (code "50") (name "unconnected-(U2A-PC8-Pad65)") (class "Default")
      (node (ref "U2") (pin "65") (pinfunction "PC8_65") (pintype "bidirectional"))
    )
    (net (code "51") (name "unconnected-(U2A-PC9-Pad66)") (class "Default")
      (node (ref "U2") (pin "66") (pinfunction "PC9_66") (pintype "bidirectional"))
    )
    (net (code "52") (name "unconnected-(U2A-PC10-Pad78)") (class "Default")
      (node (ref "U2") (pin "78") (pinfunction "PC10_78") (pintype "bidirectional"))
    )
    (net (code "53") (name "unconnected-(U2A-PC11-Pad79)") (class "Default")
      (node (ref "U2") (pin "79") (pinfunction "PC11_79") (pintype "bidirectional"))
    )
    (net (code "54") (name "unconnected-(U2A-PC12-Pad80)") (class "Default")
      (node (ref "U2") (pin "80") (pinfunction "PC12_80") (pintype "bidirectional"))
    )
    (net (code "55") (name "unconnected-(U2A-PC13-Pad7)") (class "Default")
      (node (ref "U2") (pin "7") (pinfunction "PC13_7") (pintype "bidirectional"))
    )
    (net (code "56") (name "unconnected-(U2A-PD0-Pad81)") (class "Default")
      (node (ref "U2") (pin "81") (pinfunction "PD0_81") (pintype "bidirectional"))
    )
    (net (code "57") (name "unconnected-(U2A-PD1-Pad82)") (class "Default")
      (node (ref "U2") (pin "82") (pinfunction "PD1_82") (pintype "bidirectional"))
    )
    (net (code "58") (name "unconnected-(U2A-PD2-Pad83)") (class "Default")
      (node (ref "U2") (pin "83") (pinfunction "PD2_83") (pintype "bidirectional"))
    )
    (net (code "59") (name "unconnected-(U2A-PD3-Pad84)") (class "Default")
      (node (ref "U2") (pin "84") (pinfunction "PD3_84") (pintype "bidirectional"))
    )
    (net (code "60") (name "unconnected-(U2A-PD4-Pad85)") (class "Default")
      (node (ref "U2") (pin "85") (pinfunction "PD4_85") (pintype "bidirectional"))
    )
    (net (code "61") (name "unconnected-(U2A-PD5-Pad86)") (class "Default")
      (node (ref "U2") (pin "86") (pinfunction "PD5_86") (pintype "bidirectional"))
    )
    (net (code "62") (name "unconnected-(U2A-PD6-Pad87)") (class "Default")
      (node (ref "U2") (pin "87") (pinfunction "PD6_87") (pintype "bidirectional"))
    )
    (net (code "63") (name "unconnected-(U2A-PD7-Pad88)") (class "Default")
      (node (ref "U2") (pin "88") (pinfunction "PD7_88") (pintype "bidirectional"))
    )
    (net (code "64") (name "unconnected-(U2A-PD8-Pad55)") (class "Default")
      (node (ref "U2") (pin "55") (pinfunction "PD8_55") (pintype "bidirectional"))
    )
    (net (code "65") (name "unconnected-(U2A-PD9-Pad56)") (class "Default")
      (node (ref "U2") (pin "56") (pinfunction "PD9_56") (pintype "bidirectional"))
    )
    (net (code "66") (name "unconnected-(U2A-PD10-Pad57)") (class "Default")
      (node (ref "U2") (pin "57") (pinfunction "PD10_57") (pintype "bidirectional"))
    )
    (net (code "67") (name "unconnected-(U2A-PD11-Pad58)") (class "Default")
      (node (ref "U2") (pin "58") (pinfunction "PD11_58") (pintype "bidirectional"))
    )
    (net (code "68") (name "unconnected-(U2A-PD12-Pad59)") (class "Default")
      (node (ref "U2") (pin "59") (pinfunction "PD12_59") (pintype "bidirectional"))
    )
    (net (code "69") (name "unconnected-(U2A-PD13-Pad60)") (class "Default")
      (node (ref "U2") (pin "60") (pinfunction "PD13_60") (pintype "bidirectional"))
    )
    (net (code "70") (name "unconnected-(U2A-PD14-Pad61)") (class "Default")
      (node (ref "U2") (pin "61") (pinfunction "PD14_61") (pintype "bidirectional"))
    )
    (net (code "71") (name "unconnected-(U2A-PD15-Pad62)") (class "Default")
      (node (ref "U2") (pin "62") (pinfunction "PD15_62") (pintype "bidirectional"))
    )
    (net (code "72") (name "unconnected-(U2A-PE0-Pad97)") (class "Default")
      (node (ref "U2") (pin "97") (pinfunction "PE0_97") (pintype "bidirectional"))
    )
    (net (code "73") (name "unconnected-(U2A-PE1-Pad98)") (class "Default")
      (node (ref "U2") (pin "98") (pinfunction "PE1_98") (pintype "bidirectional"))
    )
    (net (code "74") (name "unconnected-(U2A-PE2-Pad1)") (class "Default")
      (node (ref "U2") (pin "1") (pinfunction "PE2_1") (pintype "bidirectional"))
    )
    (net (code "75") (name "unconnected-(U2A-PE3-Pad2)") (class "Default")
      (node (ref "U2") (pin "2") (pinfunction "PE3_2") (pintype "bidirectional"))
    )
    (net (code "76") (name "unconnected-(U2A-PE4-Pad3)") (class "Default")
      (node (ref "U2") (pin "3") (pinfunction "PE4_3") (pintype "bidirectional"))
    )
    (net (code "77") (name "unconnected-(U2A-PE5-Pad4)") (class "Default")
      (node (ref "U2") (pin "4") (pinfunction "PE5_4") (pintype "bidirectional"))
    )
    (net (code "78") (name "unconnected-(U2A-PE6-Pad5)") (class "Default")
      (node (ref "U2") (pin "5") (pinfunction "PE6_5") (pintype "bidirectional"))
    )
    (net (code "79") (name "unconnected-(U2A-PE7-Pad38)") (class "Default")
      (node (ref "U2") (pin "38") (pinfunction "PE7_38") (pintype "bidirectional"))
    )
    (net (code "80") (name "unconnected-(U2A-PE8-Pad39)") (class "Default")
      (node (ref "U2") (pin "39") (pinfunction "PE8_39") (pintype "bidirectional"))
    )
    (net (code "81") (name "unconnected-(U2A-PE9-Pad40)") (class "Default")
      (node (ref "U2") (pin "40") (pinfunction "PE9_40") (pintype "bidirectional"))
    )
    (net (code "82") (name "unconnected-(U2A-PE10-Pad41)") (class "Default")
      (node (ref "U2") (pin "41") (pinfunction "PE10_41") (pintype "bidirectional"))
    )
    (net (code "83") (name "unconnected-(U2A-PE11-Pad42)") (class "Default")
      (node (ref "U2") (pin "42") (pinfunction "PE11_42") (pintype "bidirectional"))
    )
    (net (code "84") (name "unconnected-(U2A-PE12-Pad43)") (class "Default")
      (node (ref "U2") (pin "43") (pinfunction "PE12_43") (pintype "bidirectional"))
    )
    (net (code "85") (name "unconnected-(U2A-PE13-Pad44)") (class "Default")
      (node (ref "U2") (pin "44") (pinfunction "PE13_44") (pintype "bidirectional"))
    )
    (net (code "86") (name "unconnected-(U2A-PE14-Pad45)") (class "Default")
      (node (ref "U2") (pin "45") (pinfunction "PE14_45") (pintype "bidirectional"))
    )
    (net (code "87") (name "unconnected-(U2A-PE15-Pad46)") (class "Default")
      (node (ref "U2") (pin "46") (pinfunction "PE15_46") (pintype "bidirectional"))
    )
    (net (code "88") (name "unconnected-(U2A-PF2-Pad19)") (class "Default")
      (node (ref "U2") (pin "19") (pinfunction "PF2_19") (pintype "bidirectional"))
    )
    (net (code "89") (name "unconnected-(U2A-PF4-Pad27)") (class "Default")
      (node (ref "U2") (pin "27") (pinfunction "PF4_27") (pintype "bidirectional"))
    )
    (net (code "90") (name "unconnected-(U2A-PF6-Pad73)") (class "Default")
      (node (ref "U2") (pin "73") (pinfunction "PF6_73") (pintype "bidirectional"))
    )
    (net (code "91") (name "unconnected-(U2A-PF9-Pad10)") (class "Default")
      (node (ref "U2") (pin "10") (pinfunction "PF9_10") (pintype "bidirectional"))
    )
    (net (code "92") (name "unconnected-(U2A-PF10-Pad11)") (class "Default")
      (node (ref "U2") (pin "11") (pinfunction "PF10_11") (pintype "bidirectional"))
    )
    (net (code "93") (name "unconnected-(U2B-VBAT-Pad6)") (class "Default")
      (node (ref "U2") (pin "6") (pinfunction "VBAT_6") (pintype "power_in"))
    )
    (net (code "94") (name "unconnected-(U2B-VREF+-Pad21)") (class "Default")
      (node (ref "U2") (pin "21") (pinfunction "VREF+_21") (pintype "power_in"))
    )
  )
)
